# Sensors.net
KiCad netlist of a schematic drawn in Altium Designer
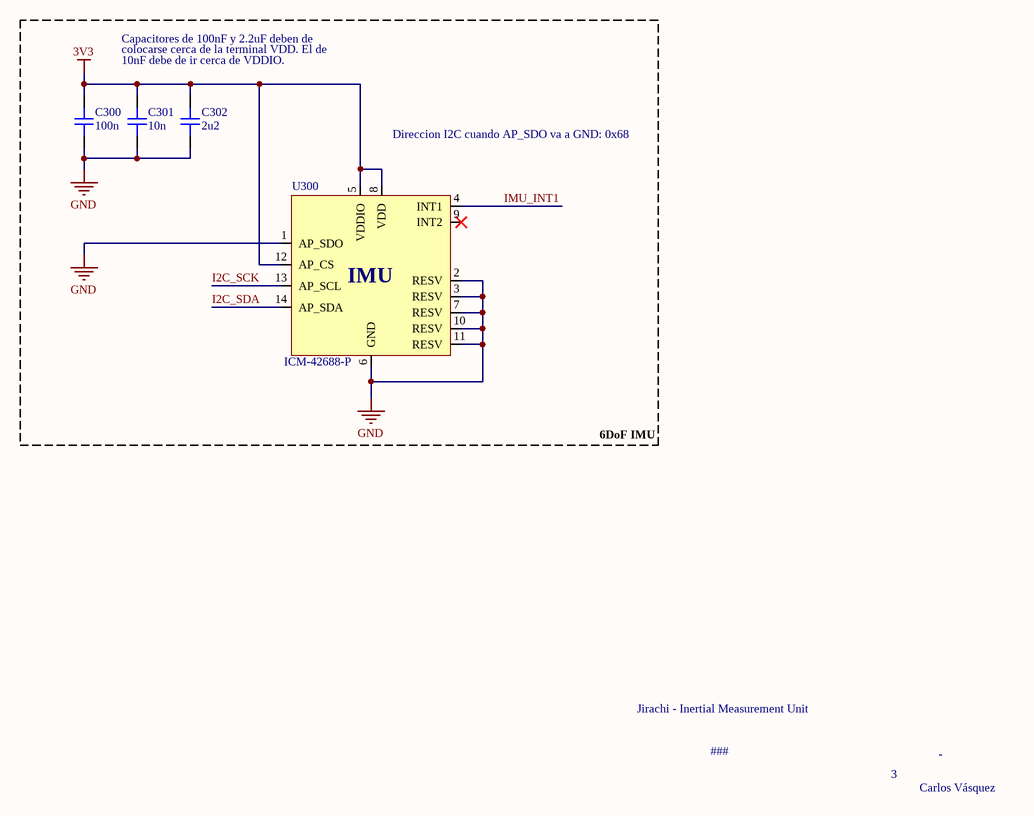
[diagram p0: Sensors.SchDoc]

(export (version "E")
  (design (tool "Eeschema 10.0.6"))
  (components
    (comp (ref "C300")
      (value "100n")
      (footprint "CAP_0402")
      (description "Capacitor SMD 0402")
      (libsource (lib "Schematic-Lib-PhilsLab") (part "CAP_0402"))
    )
    (comp (ref "C301")
      (value "10n")
      (footprint "CAP_0402")
      (description "Capacitor SMD 0402")
      (libsource (lib "Schematic-Lib-PhilsLab") (part "CAP_0402"))
    )
    (comp (ref "C302")
      (value "2u2")
      (footprint "CAP_0402")
      (description "Capacitor SMD 0402")
      (libsource (lib "Schematic-Lib-PhilsLab") (part "CAP_0402"))
    )
    (comp (ref "U300")
      (value "ICM-42688-P")
      (footprint "LGA14 (2.5mm x 3mm)")
      (description "6-axis MEMS IMU (Accelerometer & Gyroscope)")
      (libsource (lib "TerreneitorLib") (part "ICM-42688-P"))
    )
  )
  (nets
    (net (code "1") (name "/I2C_SCK") (class "Default")
      (node (ref "U300") (pin "13") (pinfunction "AP_SCL_13") (pintype "passive"))
    )
    (net (code "2") (name "/I2C_SDA") (class "Default")
      (node (ref "U300") (pin "14") (pinfunction "AP_SDA_14") (pintype "passive"))
    )
    (net (code "3") (name "/IMU_INT1") (class "Default")
      (node (ref "U300") (pin "4") (pinfunction "INT1_4") (pintype "passive"))
    )
    (net (code "4") (name "3V3") (class "Default")
      (node (ref "C300") (pin "2") (pinfunction "2_2") (pintype "passive"))
      (node (ref "C301") (pin "2") (pinfunction "2_2") (pintype "passive"))
      (node (ref "C302") (pin "2") (pinfunction "2_2") (pintype "passive"))
      (node (ref "U300") (pin "12") (pinfunction "AP_CS_12") (pintype "passive"))
      (node (ref "U300") (pin "5") (pinfunction "VDDIO_5") (pintype "passive"))
      (node (ref "U300") (pin "8") (pinfunction "VDD_8") (pintype "passive"))
    )
    (net (code "5") (name "GND") (class "Default")
      (node (ref "C300") (pin "1") (pinfunction "1_1") (pintype "passive"))
      (node (ref "C301") (pin "1") (pinfunction "1_1") (pintype "passive"))
      (node (ref "C302") (pin "1") (pinfunction "1_1") (pintype "passive"))
      (node (ref "U300") (pin "1") (pinfunction "AP_SDO_1") (pintype "passive"))
      (node (ref "U300") (pin "10") (pinfunction "RESV_10") (pintype "passive"))
      (node (ref "U300") (pin "11") (pinfunction "RESV_11") (pintype "passive"))
      (node (ref "U300") (pin "2") (pinfunction "RESV_2") (pintype "passive"))
      (node (ref "U300") (pin "3") (pinfunction "RESV_3") (pintype "passive"))
      (node (ref "U300") (pin "6") (pinfunction "GND_6") (pintype "passive"))
      (node (ref "U300") (pin "7") (pinfunction "RESV_7") (pintype "passive"))
    )
    (net (code "6") (name "unconnected-(U300-INT2-Pad9)") (class "Default")
      (node (ref "U300") (pin "9") (pinfunction "INT2_9") (pintype "passive+no_connect"))
    )
  )
)
